# MB1297_NFC_SAFE.net
KiCad netlist of a schematic drawn in Altium Designer
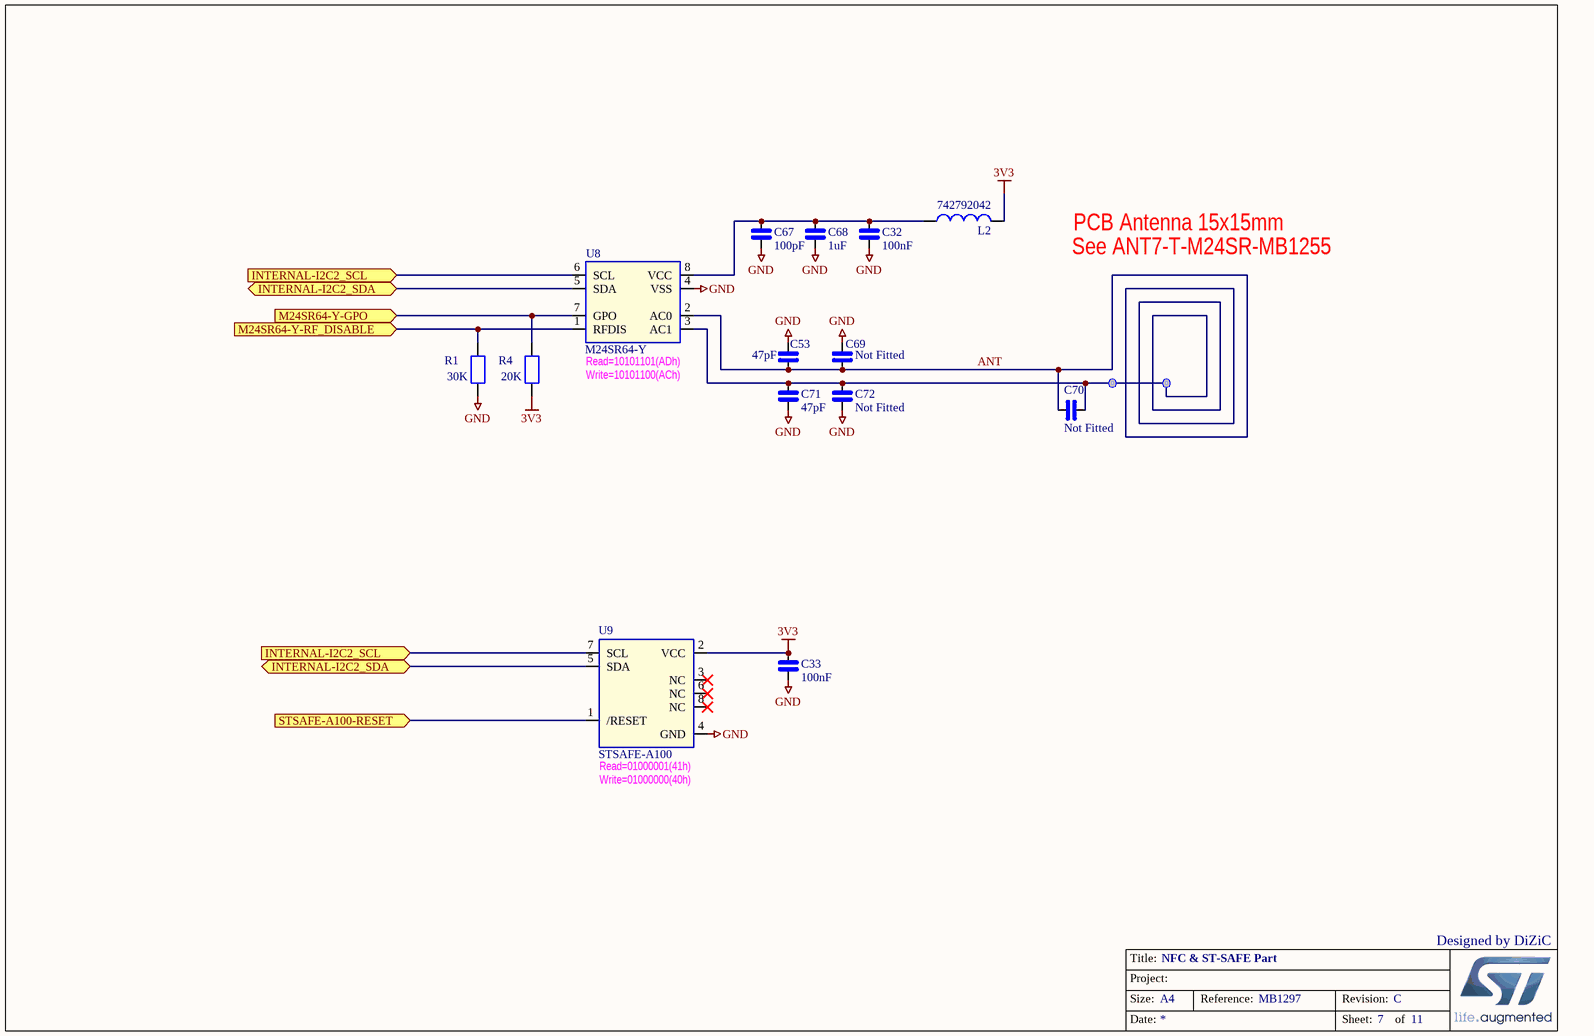
[diagram p0: MB1297_NFC_SAFE.SchDoc]

(export (version "E")
  (design (tool "Eeschema 10.0.6"))
  (components
    (comp (ref "C32")
      (value "100nF")
      (footprint "0402_CAP_NPOL")
      (description "Capacitor_not polarized")
      (libsource (lib "ST_Lib3D") (part "CAP_NPOL"))
    )
    (comp (ref "C33")
      (value "100nF")
      (footprint "0402_CAP_NPOL")
      (description "Capacitor_not polarized")
      (libsource (lib "ST_Lib3D") (part "CAP_NPOL"))
    )
    (comp (ref "C53")
      (value "47pF")
      (footprint "0402_CAP_NPOL")
      (description "Capacitor_not polarized")
      (libsource (lib "ST_Lib3D") (part "CAP_NPOL"))
    )
    (comp (ref "C67")
      (value "100pF")
      (footprint "0402_CAP_NPOL")
      (description "Capacitor_not polarized")
      (libsource (lib "ST_Lib3D") (part "CAP_NPOL"))
    )
    (comp (ref "C68")
      (value "1uF")
      (footprint "0402_CAP_NPOL")
      (description "Capacitor_not polarized")
      (libsource (lib "ST_Lib3D") (part "CAP_NPOL"))
    )
    (comp (ref "C69")
      (value "Not Fitted")
      (footprint "0402_CAP_NPOL")
      (description "Capacitor_not polarized")
      (libsource (lib "ST_Lib3D") (part "CAP_NPOL"))
    )
    (comp (ref "C70")
      (value "Not Fitted")
      (footprint "0402_CAP_NPOL")
      (description "Capacitor_not polarized")
      (libsource (lib "ST_Lib3D") (part "CAP_NPOL"))
    )
    (comp (ref "C71")
      (value "47pF")
      (footprint "0402_CAP_NPOL")
      (description "Capacitor_not polarized")
      (libsource (lib "ST_Lib3D") (part "CAP_NPOL"))
    )
    (comp (ref "C72")
      (value "Not Fitted")
      (footprint "0402_CAP_NPOL")
      (description "Capacitor_not polarized")
      (libsource (lib "ST_Lib3D") (part "CAP_NPOL"))
    )
    (comp (ref "L2")
      (value "742792042")
      (footprint "0603L")
      (description "Inductor")
      (fields (field (name "PUBLISHER") "Altium Limited"))
      (libsource (lib "Miscellaneous Devices") (part "Inductor"))
    )
    (comp (ref "R1")
      (value "30K")
      (footprint "0402_RES")
      (description "Resistor")
      (libsource (lib "ST_Lib3D") (part "RES"))
    )
    (comp (ref "R4")
      (value "20K")
      (footprint "0402_RES")
      (description "Resistor")
      (libsource (lib "ST_Lib3D") (part "RES"))
    )
    (comp (ref "U8")
      (value "M24SR64-Y")
      (footprint "SOP8")
      (description "M24SR64-Y  64K_EEPROM NFC/RFID")
      (libsource (lib "ST_Lib3D") (part "M24SR64-Y"))
    )
    (comp (ref "U9")
      (value "STSAFE-A100")
      (footprint "SOP8")
      (libsource (lib "ST_Lib3D") (part "STSAFE-A100"))
    )
  )
  (nets
    (net (code "1") (name "/ANT") (class "Default")
      (node (ref "C53") (pin "1") (pinfunction "1_1") (pintype "passive"))
      (node (ref "C69") (pin "1") (pinfunction "1_1") (pintype "passive"))
      (node (ref "C70") (pin "1") (pinfunction "1_1") (pintype "passive"))
      (node (ref "C70") (pin "2") (pinfunction "2_2") (pintype "passive"))
      (node (ref "C71") (pin "1") (pinfunction "1_1") (pintype "passive"))
      (node (ref "C72") (pin "1") (pinfunction "1_1") (pintype "passive"))
      (node (ref "U8") (pin "2") (pinfunction "AC0_2") (pintype "passive"))
      (node (ref "U8") (pin "3") (pinfunction "AC1_3") (pintype "passive"))
    )
    (net (code "2") (name "/INTERNAL-I2C2_SCL") (class "Default")
      (node (ref "U8") (pin "6") (pinfunction "SCL_6") (pintype "passive"))
      (node (ref "U9") (pin "7") (pinfunction "SCL_7") (pintype "passive"))
    )
    (net (code "3") (name "/INTERNAL-I2C2_SDA") (class "Default")
      (node (ref "U8") (pin "5") (pinfunction "SDA_5") (pintype "passive"))
      (node (ref "U9") (pin "5") (pinfunction "SDA_5") (pintype "passive"))
    )
    (net (code "4") (name "/M24SR64-Y-GPO") (class "Default")
      (node (ref "R4") (pin "2") (pinfunction "2_2") (pintype "passive"))
      (node (ref "U8") (pin "7") (pinfunction "GPO_7") (pintype "passive"))
    )
    (net (code "5") (name "/M24SR64-Y-RF_DISABLE") (class "Default")
      (node (ref "R1") (pin "2") (pinfunction "2_2") (pintype "passive"))
      (node (ref "U8") (pin "1") (pinfunction "RFDIS_1") (pintype "passive"))
    )
    (net (code "6") (name "/STSAFE-A100-RESET") (class "Default")
      (node (ref "U9") (pin "1") (pinfunction "/RESET_1") (pintype "passive"))
    )
    (net (code "7") (name "3V3") (class "Default")
      (node (ref "C33") (pin "1") (pinfunction "1_1") (pintype "passive"))
      (node (ref "L2") (pin "2") (pinfunction "2_2") (pintype "passive"))
      (node (ref "R4") (pin "1") (pinfunction "1_1") (pintype "passive"))
      (node (ref "U9") (pin "2") (pinfunction "VCC_2") (pintype "passive"))
    )
    (net (code "8") (name "GND") (class "Default")
      (node (ref "C32") (pin "2") (pinfunction "2_2") (pintype "passive"))
      (node (ref "C33") (pin "2") (pinfunction "2_2") (pintype "passive"))
      (node (ref "C53") (pin "2") (pinfunction "2_2") (pintype "passive"))
      (node (ref "C67") (pin "2") (pinfunction "2_2") (pintype "passive"))
      (node (ref "C68") (pin "2") (pinfunction "2_2") (pintype "passive"))
      (node (ref "C69") (pin "2") (pinfunction "2_2") (pintype "passive"))
      (node (ref "C71") (pin "2") (pinfunction "2_2") (pintype "passive"))
      (node (ref "C72") (pin "2") (pinfunction "2_2") (pintype "passive"))
      (node (ref "R1") (pin "1") (pinfunction "1_1") (pintype "passive"))
      (node (ref "U8") (pin "4") (pinfunction "VSS_4") (pintype "passive"))
      (node (ref "U9") (pin "4") (pinfunction "GND_4") (pintype "passive"))
    )
    (net (code "9") (name "Net-(U8-VCC)") (class "Default")
      (node (ref "C32") (pin "1") (pinfunction "1_1") (pintype "passive"))
      (node (ref "C67") (pin "1") (pinfunction "1_1") (pintype "passive"))
      (node (ref "C68") (pin "1") (pinfunction "1_1") (pintype "passive"))
      (node (ref "L2") (pin "1") (pinfunction "1_1") (pintype "passive"))
      (node (ref "U8") (pin "8") (pinfunction "VCC_8") (pintype "passive"))
    )
    (net (code "10") (name "unconnected-(U9-NC-Pad3)") (class "Default")
      (node (ref "U9") (pin "3") (pinfunction "NC_3") (pintype "passive+no_connect"))
    )
    (net (code "11") (name "unconnected-(U9-NC-Pad6)") (class "Default")
      (node (ref "U9") (pin "6") (pinfunction "NC_6") (pintype "passive+no_connect"))
    )
    (net (code "12") (name "unconnected-(U9-NC-Pad8)") (class "Default")
      (node (ref "U9") (pin "8") (pinfunction "NC_8") (pintype "passive+no_connect"))
    )
  )
)
